# smartGarden_Pow_Rev01.net
KiCad netlist of a schematic drawn in Altium Designer
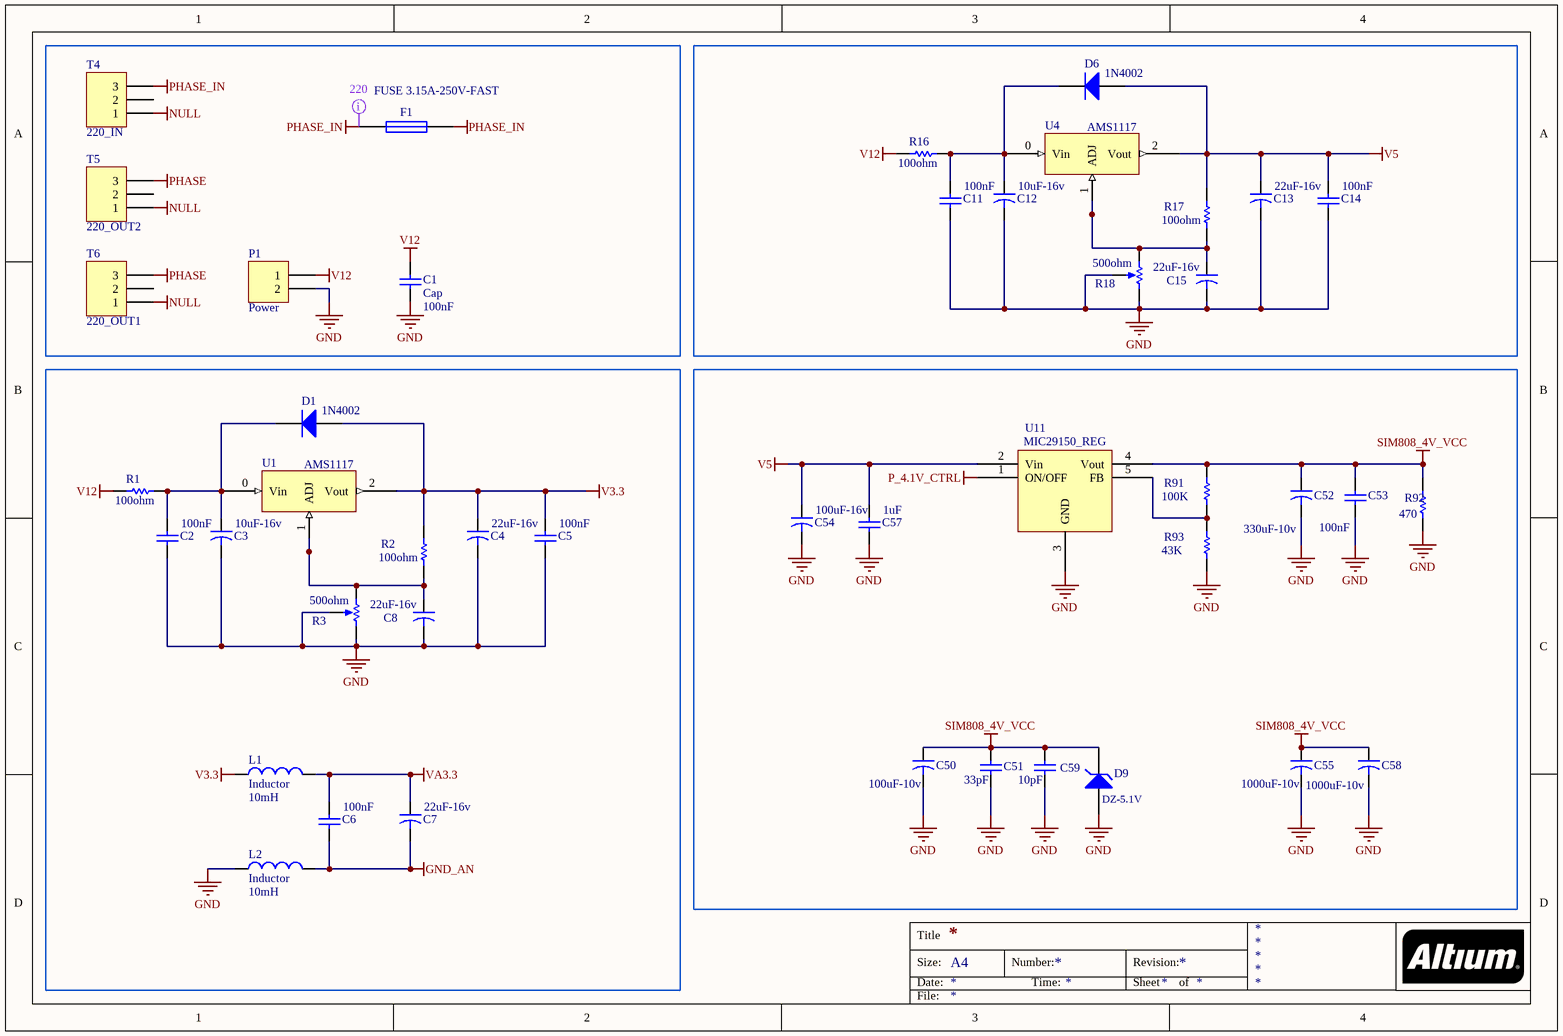
[diagram p0: smartGarden_Pow_Rev01.SchDoc]

(export (version "E")
  (design (tool "Eeschema 10.0.6"))
  (components
    (comp (ref "C1")
      (value "Cap")
      (footprint "0805_smd")
      (description "Capacitor")
      (fields (field (name "ALTIUM_VALUE") "100nF") (field (name "PUBLISHER") "Altium Limited"))
      (libsource (lib "Miscellaneous Devices") (part "Cap"))
    )
    (comp (ref "C2")
      (value "100nF")
      (footprint "0805_smd")
      (description "Capacitor")
      (fields (field (name "Comment") "Cap") (field (name "PUBLISHER") "Altium Limited"))
      (libsource (lib "Miscellaneous Devices") (part "Cap"))
    )
    (comp (ref "C3")
      (value "10uF-16v")
      (footprint "CAPR5-4X5")
      (description "Capacitor")
      (fields (field (name "Comment") "Cap2") (field (name "PUBLISHER") "Altium Limited"))
      (libsource (lib "Miscellaneous Devices") (part "Cap2"))
    )
    (comp (ref "C4")
      (value "22uF-16v")
      (footprint "C100uF/25V")
      (description "Capacitor")
      (fields (field (name "Comment") "Cap2") (field (name "PUBLISHER") "Altium Limited"))
      (libsource (lib "Miscellaneous Devices") (part "Cap2"))
    )
    (comp (ref "C5")
      (value "100nF")
      (footprint "0805_smd")
      (description "Capacitor")
      (fields (field (name "Comment") "Cap") (field (name "PUBLISHER") "Altium Limited"))
      (libsource (lib "Miscellaneous Devices") (part "Cap"))
    )
    (comp (ref "C6")
      (value "100nF")
      (footprint "0805_smd")
      (description "Capacitor")
      (fields (field (name "Comment") "Cap") (field (name "PUBLISHER") "Altium Limited"))
      (libsource (lib "Miscellaneous Devices") (part "Cap"))
    )
    (comp (ref "C7")
      (value "22uF-16v")
      (footprint "C100uF/25V")
      (description "Capacitor")
      (fields (field (name "Comment") "Cap2") (field (name "PUBLISHER") "Altium Limited"))
      (libsource (lib "Miscellaneous Devices") (part "Cap2"))
    )
    (comp (ref "C8")
      (value "22uF-16v")
      (footprint "C100uF/25V")
      (description "Capacitor")
      (fields (field (name "Comment") "Cap2") (field (name "PUBLISHER") "Altium Limited"))
      (libsource (lib "Miscellaneous Devices") (part "Cap2"))
    )
    (comp (ref "C11")
      (value "100nF")
      (footprint "0805_smd")
      (description "Capacitor")
      (fields (field (name "Comment") "Cap") (field (name "PUBLISHER") "Altium Limited"))
      (libsource (lib "Miscellaneous Devices") (part "Cap"))
    )
    (comp (ref "C12")
      (value "10uF-16v")
      (footprint "CAPR5-4X5")
      (description "Capacitor")
      (fields (field (name "Comment") "Cap2") (field (name "PUBLISHER") "Altium Limited"))
      (libsource (lib "Miscellaneous Devices") (part "Cap2"))
    )
    (comp (ref "C13")
      (value "22uF-16v")
      (footprint "C100uF/25V")
      (description "Capacitor")
      (fields (field (name "Comment") "Cap2") (field (name "PUBLISHER") "Altium Limited"))
      (libsource (lib "Miscellaneous Devices") (part "Cap2"))
    )
    (comp (ref "C14")
      (value "100nF")
      (footprint "0805_smd")
      (description "Capacitor")
      (fields (field (name "Comment") "Cap") (field (name "PUBLISHER") "Altium Limited"))
      (libsource (lib "Miscellaneous Devices") (part "Cap"))
    )
    (comp (ref "C15")
      (value "22uF-16v")
      (footprint "C100uF/25V")
      (description "Capacitor")
      (fields (field (name "Comment") "Cap2") (field (name "PUBLISHER") "Altium Limited"))
      (libsource (lib "Miscellaneous Devices") (part "Cap2"))
    )
    (comp (ref "C50")
      (value "100uF-10v")
      (footprint "CAPR5-4X5")
      (description "Capacitor")
      (fields (field (name "Comment") "Cap2") (field (name "PUBLISHER") "Altium Limited"))
      (libsource (lib "Miscellaneous Devices") (part "Cap2"))
    )
    (comp (ref "C51")
      (value "33pF")
      (footprint "0805_smd")
      (description "Capacitor")
      (fields (field (name "PUBLISHER") "Altium Limited"))
      (libsource (lib "Miscellaneous Devices") (part "Cap"))
    )
    (comp (ref "C52")
      (value "330uF-10v")
      (footprint "CAPR5-4X5")
      (description "Capacitor")
      (fields (field (name "Comment") "Cap2") (field (name "PUBLISHER") "Altium Limited"))
      (libsource (lib "Miscellaneous Devices") (part "Cap2"))
    )
    (comp (ref "C53")
      (value "100nF")
      (footprint "0805_smd")
      (description "Capacitor")
      (fields (field (name "Comment") "Cap") (field (name "PUBLISHER") "Altium Limited"))
      (libsource (lib "Miscellaneous Devices") (part "Cap"))
    )
    (comp (ref "C54")
      (value "100uF-16v")
      (footprint "C100uF/25V")
      (description "Capacitor")
      (fields (field (name "Comment") "Cap2") (field (name "PUBLISHER") "Altium Limited"))
      (libsource (lib "Miscellaneous Devices") (part "Cap2"))
    )
    (comp (ref "C55")
      (value "1000uF-10v")
      (footprint "CAPR5-4X5")
      (description "Capacitor")
      (fields (field (name "Comment") "Cap2") (field (name "PUBLISHER") "Altium Limited"))
      (libsource (lib "Miscellaneous Devices") (part "Cap2"))
    )
    (comp (ref "C57")
      (value "1uF")
      (footprint "0805_smd")
      (description "Capacitor")
      (fields (field (name "Comment") "Cap") (field (name "PUBLISHER") "Altium Limited"))
      (libsource (lib "Miscellaneous Devices") (part "Cap"))
    )
    (comp (ref "C58")
      (value "1000uF-10v")
      (footprint "CAPR5-4X5")
      (description "Capacitor")
      (fields (field (name "Comment") "Cap2") (field (name "PUBLISHER") "Altium Limited"))
      (libsource (lib "Miscellaneous Devices") (part "Cap2"))
    )
    (comp (ref "C59")
      (value "10pF")
      (footprint "0805_smd")
      (description "Capacitor")
      (fields (field (name "PUBLISHER") "Altium Limited"))
      (libsource (lib "Miscellaneous Devices") (part "Cap"))
    )
    (comp (ref "D1")
      (value "1N4002")
      (footprint "7227_SMD")
      (description "1 Amp General Purpose Rectifier")
      (fields (field (name "PUBLISHER") "Altium Limited"))
      (libsource (lib "Miscellaneous Devices") (part "Diode 1N4002"))
    )
    (comp (ref "D6")
      (value "1N4002")
      (footprint "7227_SMD")
      (description "1 Amp General Purpose Rectifier")
      (fields (field (name "PUBLISHER") "Altium Limited"))
      (libsource (lib "Miscellaneous Devices") (part "Diode 1N4002"))
    )
    (comp (ref "D9")
      (value "DZ-5.1V")
      (footprint "MLL34_SMD")
      (description "Zener Diode")
      (fields (field (name "PUBLISHER") "Altium Limited"))
      (libsource (lib "Miscellaneous Devices") (part "D Zener"))
    )
    (comp (ref "F1")
      (value "FUSE 3.15A-250V-FAST")
      (footprint "FUSE1")
      (description "Fuse")
      (libsource (lib "*") (part "FUSE1"))
    )
    (comp (ref "L1")
      (value "Inductor")
      (footprint "0402-A")
      (fields (field (name "ALTIUM_VALUE") "10mH") (field (name "PUBLISHER") "Altium Limited"))
      (libsource (lib "Miscellaneous Devices") (part "Inductor"))
    )
    (comp (ref "L2")
      (value "Inductor")
      (footprint "0402-A")
      (fields (field (name "ALTIUM_VALUE") "10mH") (field (name "PUBLISHER") "Altium Limited"))
      (libsource (lib "Miscellaneous Devices") (part "Inductor"))
    )
    (comp (ref "P1")
      (value "Power")
      (footprint "PCON_L2")
      (description "Header, 2-Pin")
      (fields (field (name "PUBLISHER") "Altium Limited"))
      (libsource (lib "Miscellaneous Connectors") (part "Header 2"))
    )
    (comp (ref "R1")
      (value "100ohm")
      (footprint "1206_SMD")
      (description "Resistor")
      (fields (field (name "Comment") "Res1") (field (name "PUBLISHER") "Altium Limited"))
      (libsource (lib "Miscellaneous Devices") (part "Res1"))
    )
    (comp (ref "R2")
      (value "100ohm")
      (footprint "0805_smd")
      (description "Resistor")
      (fields (field (name "Comment") "Res1") (field (name "PUBLISHER") "Altium Limited"))
      (libsource (lib "Miscellaneous Devices") (part "Res1"))
    )
    (comp (ref "R3")
      (value "500ohm")
      (footprint "Trimmer Pot")
      (description "Potentiometer")
      (fields (field (name "Comment") "RPot") (field (name "PUBLISHER") "Altium Limited"))
      (libsource (lib "Miscellaneous Devices") (part "RPot"))
    )
    (comp (ref "R16")
      (value "100ohm")
      (footprint "1206_SMD")
      (description "Resistor")
      (fields (field (name "Comment") "Res1") (field (name "PUBLISHER") "Altium Limited"))
      (libsource (lib "Miscellaneous Devices") (part "Res1"))
    )
    (comp (ref "R17")
      (value "100ohm")
      (footprint "0805_smd")
      (description "Resistor")
      (fields (field (name "Comment") "Res1") (field (name "PUBLISHER") "Altium Limited"))
      (libsource (lib "Miscellaneous Devices") (part "Res1"))
    )
    (comp (ref "R18")
      (value "500ohm")
      (footprint "Trimmer Pot")
      (description "Potentiometer")
      (fields (field (name "Comment") "RPot") (field (name "PUBLISHER") "Altium Limited"))
      (libsource (lib "Miscellaneous Devices") (part "RPot"))
    )
    (comp (ref "R91")
      (value "100K")
      (footprint "0805_smd")
      (description "Resistor")
      (fields (field (name "Comment") "Res1") (field (name "PUBLISHER") "Altium Limited"))
      (libsource (lib "Miscellaneous Devices") (part "Res1"))
    )
    (comp (ref "R92")
      (value "470")
      (footprint "1206_SMD")
      (description "Resistor")
      (fields (field (name "Comment") "Res1") (field (name "PUBLISHER") "Altium Limited"))
      (libsource (lib "Miscellaneous Devices") (part "Res1"))
    )
    (comp (ref "R93")
      (value "43K")
      (footprint "0805_smd")
      (description "Resistor")
      (fields (field (name "Comment") "Res1") (field (name "PUBLISHER") "Altium Limited"))
      (libsource (lib "Miscellaneous Devices") (part "Res1"))
    )
    (comp (ref "T4")
      (value "220_IN")
      (footprint "PCON_L3")
      (description "Header, 3-Pin")
      (fields (field (name "PUBLISHER") "Altium Limited"))
      (libsource (lib "Miscellaneous Connectors") (part "Header 3"))
    )
    (comp (ref "T5")
      (value "220_OUT2")
      (footprint "PCON_L3")
      (description "Header, 3-Pin")
      (fields (field (name "PUBLISHER") "Altium Limited"))
      (libsource (lib "Miscellaneous Connectors") (part "Header 3"))
    )
    (comp (ref "T6")
      (value "220_OUT1")
      (footprint "PCON_L3")
      (description "Header, 3-Pin")
      (fields (field (name "PUBLISHER") "Altium Limited"))
      (libsource (lib "Miscellaneous Connectors") (part "Header 3"))
    )
    (comp (ref "U1") (value "AMS1117") (footprint "SOT223") (libsource (lib "MYLib524") (part "AMS1117")))
    (comp (ref "U4") (value "AMS1117") (footprint "SOT223") (libsource (lib "MYLib524") (part "AMS1117")))
    (comp (ref "U11") (value "MIC29150_REG") (libsource (lib "MYLib524") (part "MIC29150_REG")))
  )
  (nets
    (net (code "1") (name "GND") (class "Default")
      (node (ref "C1") (pin "1") (pinfunction "1_1") (pintype "passive"))
      (node (ref "C11") (pin "1") (pinfunction "1_1") (pintype "passive"))
      (node (ref "C12") (pin "2") (pinfunction "2_2") (pintype "passive"))
      (node (ref "C13") (pin "2") (pinfunction "2_2") (pintype "passive"))
      (node (ref "C14") (pin "1") (pinfunction "1_1") (pintype "passive"))
      (node (ref "C15") (pin "2") (pinfunction "2_2") (pintype "passive"))
      (node (ref "C2") (pin "1") (pinfunction "1_1") (pintype "passive"))
      (node (ref "C3") (pin "2") (pinfunction "2_2") (pintype "passive"))
      (node (ref "C4") (pin "2") (pinfunction "2_2") (pintype "passive"))
      (node (ref "C5") (pin "1") (pinfunction "1_1") (pintype "passive"))
      (node (ref "C50") (pin "2") (pinfunction "2_2") (pintype "passive"))
      (node (ref "C51") (pin "1") (pinfunction "1_1") (pintype "passive"))
      (node (ref "C52") (pin "2") (pinfunction "2_2") (pintype "passive"))
      (node (ref "C53") (pin "1") (pinfunction "1_1") (pintype "passive"))
      (node (ref "C54") (pin "2") (pinfunction "2_2") (pintype "passive"))
      (node (ref "C55") (pin "2") (pinfunction "2_2") (pintype "passive"))
      (node (ref "C57") (pin "1") (pinfunction "1_1") (pintype "passive"))
      (node (ref "C58") (pin "2") (pinfunction "2_2") (pintype "passive"))
      (node (ref "C59") (pin "1") (pinfunction "1_1") (pintype "passive"))
      (node (ref "C8") (pin "2") (pinfunction "2_2") (pintype "passive"))
      (node (ref "D9") (pin "A") (pinfunction "A_A") (pintype "passive"))
      (node (ref "L2") (pin "1") (pinfunction "1_1") (pintype "passive"))
      (node (ref "P1") (pin "2") (pinfunction "2_2") (pintype "passive"))
      (node (ref "R18") (pin "2") (pinfunction "BOT_2") (pintype "passive"))
      (node (ref "R18") (pin "3") (pinfunction "TAP_3") (pintype "passive"))
      (node (ref "R3") (pin "2") (pinfunction "BOT_2") (pintype "passive"))
      (node (ref "R3") (pin "3") (pinfunction "TAP_3") (pintype "passive"))
      (node (ref "R92") (pin "1") (pinfunction "1_1") (pintype "passive"))
      (node (ref "R93") (pin "1") (pinfunction "1_1") (pintype "passive"))
      (node (ref "U11") (pin "3") (pinfunction "GND_3") (pintype "passive"))
    )
    (net (code "2") (name "GND_AN") (class "Default")
      (node (ref "C6") (pin "1") (pinfunction "1_1") (pintype "passive"))
      (node (ref "C7") (pin "2") (pinfunction "2_2") (pintype "passive"))
      (node (ref "L2") (pin "2") (pinfunction "2_2") (pintype "passive"))
    )
    (net (code "3") (name "NULL") (class "Default")
      (node (ref "T4") (pin "1") (pinfunction "1_1") (pintype "passive"))
      (node (ref "T5") (pin "1") (pinfunction "1_1") (pintype "passive"))
      (node (ref "T6") (pin "1") (pinfunction "1_1") (pintype "passive"))
    )
    (net (code "4") (name "Net-(D1-K)") (class "Default")
      (node (ref "C2") (pin "2") (pinfunction "2_2") (pintype "passive"))
      (node (ref "C3") (pin "1") (pinfunction "1_1") (pintype "passive"))
      (node (ref "D1") (pin "2") (pinfunction "K_2") (pintype "passive"))
      (node (ref "R1") (pin "1") (pinfunction "1_1") (pintype "passive"))
      (node (ref "U1") (pin "0") (pinfunction "Vin_0") (pintype "input"))
    )
    (net (code "5") (name "Net-(D6-K)") (class "Default")
      (node (ref "C11") (pin "2") (pinfunction "2_2") (pintype "passive"))
      (node (ref "C12") (pin "1") (pinfunction "1_1") (pintype "passive"))
      (node (ref "D6") (pin "2") (pinfunction "K_2") (pintype "passive"))
      (node (ref "R16") (pin "1") (pinfunction "1_1") (pintype "passive"))
      (node (ref "U4") (pin "0") (pinfunction "Vin_0") (pintype "input"))
    )
    (net (code "6") (name "Net-(R3-TOP)") (class "Default")
      (node (ref "C8") (pin "1") (pinfunction "1_1") (pintype "passive"))
      (node (ref "R2") (pin "1") (pinfunction "1_1") (pintype "passive"))
      (node (ref "R3") (pin "1") (pinfunction "TOP_1") (pintype "passive"))
      (node (ref "U1") (pin "1") (pinfunction "ADJ_1") (pintype "input"))
    )
    (net (code "7") (name "Net-(R18-TOP)") (class "Default")
      (node (ref "C15") (pin "1") (pinfunction "1_1") (pintype "passive"))
      (node (ref "R17") (pin "1") (pinfunction "1_1") (pintype "passive"))
      (node (ref "R18") (pin "1") (pinfunction "TOP_1") (pintype "passive"))
      (node (ref "U4") (pin "1") (pinfunction "ADJ_1") (pintype "input"))
    )
    (net (code "8") (name "Net-(U11-FB)") (class "Default")
      (node (ref "R91") (pin "1") (pinfunction "1_1") (pintype "passive"))
      (node (ref "R93") (pin "2") (pinfunction "2_2") (pintype "passive"))
      (node (ref "U11") (pin "5") (pinfunction "FB_5") (pintype "passive"))
    )
    (net (code "9") (name "PHASE") (class "Default")
      (node (ref "T5") (pin "3") (pinfunction "3_3") (pintype "passive"))
      (node (ref "T6") (pin "3") (pinfunction "3_3") (pintype "passive"))
    )
    (net (code "10") (name "PHASE_IN") (class "Default")
      (node (ref "F1") (pin "1") (pinfunction "1_1") (pintype "passive"))
      (node (ref "F1") (pin "2") (pinfunction "2_2") (pintype "passive"))
      (node (ref "T4") (pin "3") (pinfunction "3_3") (pintype "passive"))
    )
    (net (code "11") (name "P_4.1V_CTRL") (class "Default")
      (node (ref "U11") (pin "1") (pinfunction "ON/OFF_1") (pintype "passive"))
    )
    (net (code "12") (name "SIM808_4V_VCC") (class "Default")
      (node (ref "C50") (pin "1") (pinfunction "1_1") (pintype "passive"))
      (node (ref "C51") (pin "2") (pinfunction "2_2") (pintype "passive"))
      (node (ref "C52") (pin "1") (pinfunction "1_1") (pintype "passive"))
      (node (ref "C53") (pin "2") (pinfunction "2_2") (pintype "passive"))
      (node (ref "C55") (pin "1") (pinfunction "1_1") (pintype "passive"))
      (node (ref "C58") (pin "1") (pinfunction "1_1") (pintype "passive"))
      (node (ref "C59") (pin "2") (pinfunction "2_2") (pintype "passive"))
      (node (ref "D9") (pin "K") (pinfunction "K_K") (pintype "passive"))
      (node (ref "R91") (pin "2") (pinfunction "2_2") (pintype "passive"))
      (node (ref "R92") (pin "2") (pinfunction "2_2") (pintype "passive"))
      (node (ref "U11") (pin "4") (pinfunction "Vout_4") (pintype "passive"))
    )
    (net (code "13") (name "V3.3") (class "Default")
      (node (ref "C4") (pin "1") (pinfunction "1_1") (pintype "passive"))
      (node (ref "C5") (pin "2") (pinfunction "2_2") (pintype "passive"))
      (node (ref "D1") (pin "1") (pinfunction "A_1") (pintype "passive"))
      (node (ref "L1") (pin "1") (pinfunction "1_1") (pintype "passive"))
      (node (ref "R2") (pin "2") (pinfunction "2_2") (pintype "passive"))
      (node (ref "U1") (pin "2") (pinfunction "Vout_2") (pintype "output"))
    )
    (net (code "14") (name "V5") (class "Default")
      (node (ref "C13") (pin "1") (pinfunction "1_1") (pintype "passive"))
      (node (ref "C14") (pin "2") (pinfunction "2_2") (pintype "passive"))
      (node (ref "C54") (pin "1") (pinfunction "1_1") (pintype "passive"))
      (node (ref "C57") (pin "2") (pinfunction "2_2") (pintype "passive"))
      (node (ref "D6") (pin "1") (pinfunction "A_1") (pintype "passive"))
      (node (ref "R17") (pin "2") (pinfunction "2_2") (pintype "passive"))
      (node (ref "U11") (pin "2") (pinfunction "Vin_2") (pintype "passive"))
      (node (ref "U4") (pin "2") (pinfunction "Vout_2") (pintype "output"))
    )
    (net (code "15") (name "V12") (class "Default")
      (node (ref "C1") (pin "2") (pinfunction "2_2") (pintype "passive"))
      (node (ref "P1") (pin "1") (pinfunction "1_1") (pintype "passive"))
      (node (ref "R1") (pin "2") (pinfunction "2_2") (pintype "passive"))
      (node (ref "R16") (pin "2") (pinfunction "2_2") (pintype "passive"))
    )
    (net (code "16") (name "VA3.3") (class "Default")
      (node (ref "C6") (pin "2") (pinfunction "2_2") (pintype "passive"))
      (node (ref "C7") (pin "1") (pinfunction "1_1") (pintype "passive"))
      (node (ref "L1") (pin "2") (pinfunction "2_2") (pintype "passive"))
    )
    (net (code "17") (name "unconnected-(T4-Pad2)") (class "Default")
      (node (ref "T4") (pin "2") (pinfunction "2_2") (pintype "passive"))
    )
    (net (code "18") (name "unconnected-(T5-Pad2)") (class "Default")
      (node (ref "T5") (pin "2") (pinfunction "2_2") (pintype "passive"))
    )
    (net (code "19") (name "unconnected-(T6-Pad2)") (class "Default")
      (node (ref "T6") (pin "2") (pinfunction "2_2") (pintype "passive"))
    )
  )
)
